# EFR32_IO_connection.net
KiCad netlist of a schematic drawn in Altium Designer
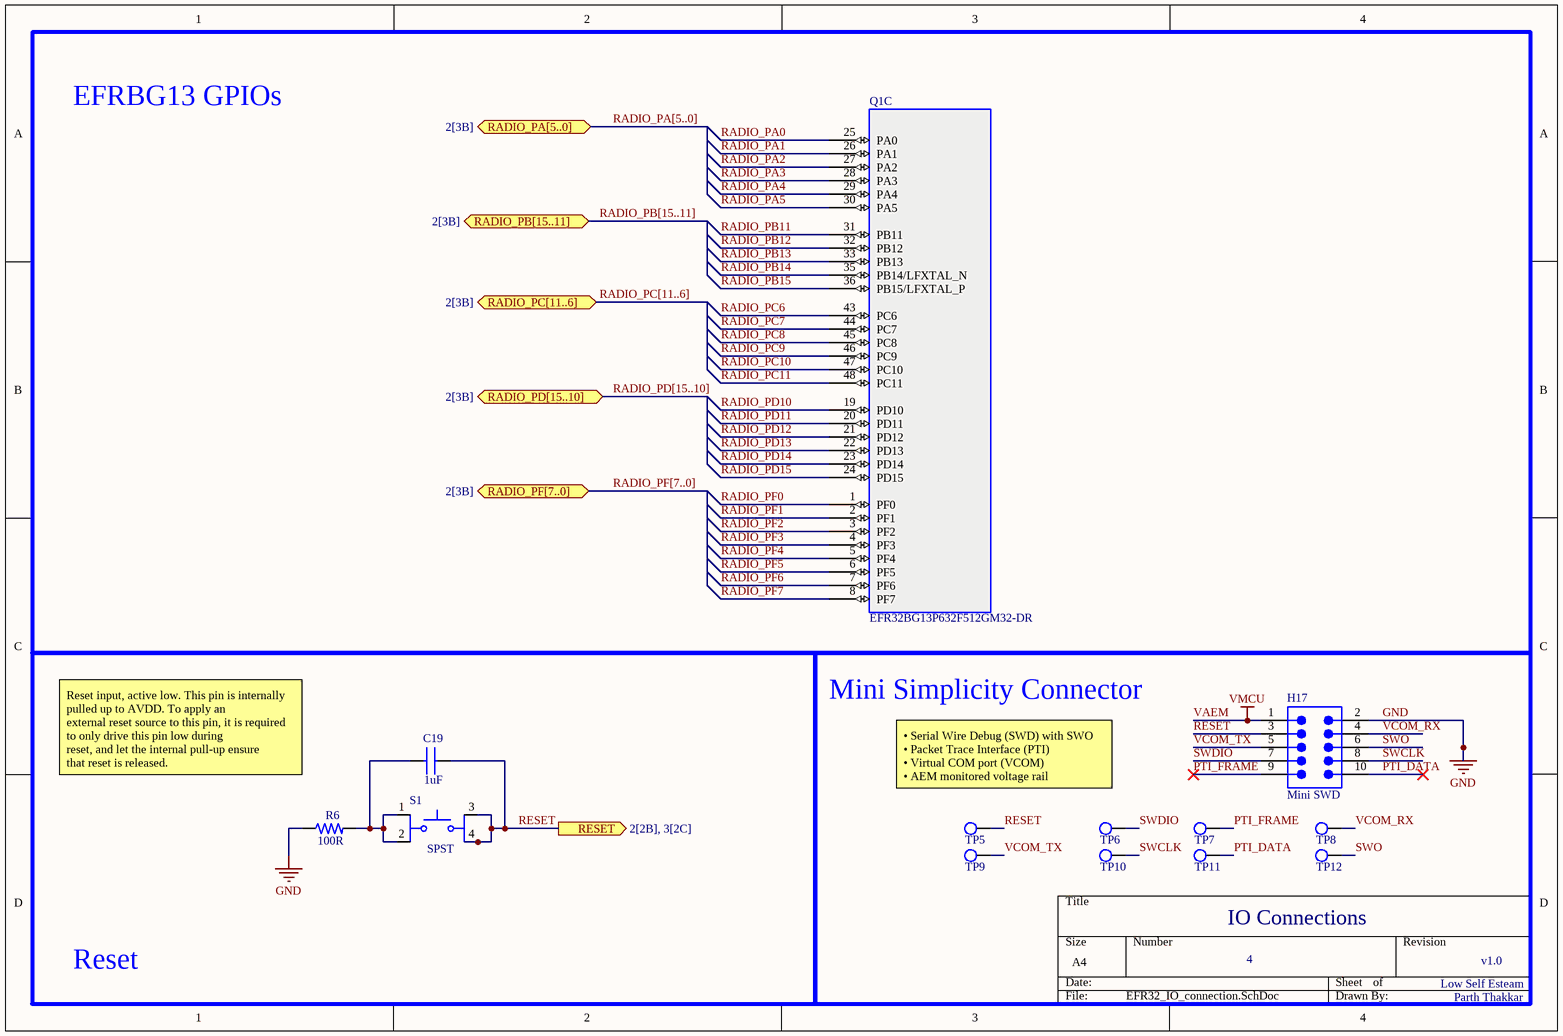
[diagram p0: EFR32_IO_connection.SchDoc]

(export (version "E")
  (design (tool "Eeschema 10.0.6"))
  (components
    (comp (ref "C19")
      (value "1uF")
      (footprint "Capacitor 0603")
      (fields
        (field (name "MANUFACTURER") "Murata")
        (field (name "MANUFACTURER PART NUMBER") "GRM188R61A105KA61D")
        (field (name "Comment") "CAP 1uF 10V 0603")
      )
      (libsource (lib "Keyboard_parts") (part "CAP 1uF 10V 0603"))
    )
    (comp (ref "H17")
      (value "Mini SWD")
      (footprint "Mini Simplicity Connector")
      (description "Mini SWD 0.05\" Pitch Connector - 10 Pin SMT Box Header")
      (fields
        (field (name "MANUFACTURER") "Adafruit Industries")
        (field (name "MANUFACTURER PART NUMBER") "4048")
      )
      (libsource (lib "Keyboard_parts") (part "Debug Connector Mini SWD - 0.05{dblquote}"))
    )
    (comp (ref "Q1")
      (value "EFR32BG13P632F512GM32-DR")
      (footprint "EFR32BG")
      (description "BLue Gecko")
      (fields (field (name "MANUFACTURER") "Silicon Labs"))
      (libsource (lib "Keyboard_parts") (part "EFR32BG13P632F512GM32-DR"))
    )
    (comp (ref "R6")
      (value "100R")
      (footprint "Resistor 0603")
      (fields
        (field (name "MANUFACTURER") "Yageo")
        (field (name "MANUFACTURER PART NUMBER") "RC0603FR-07100RL")
        (field (name "TOLERANCE") "1%")
      )
      (libsource (lib "Keyboard_parts") (part "RES 100R 0603"))
    )
    (comp (ref "S1")
      (value "SPST")
      (footprint "SPST")
      (fields
        (field (name "MANUFACTURER") "E-Switch")
        (field (name "MANUFACTURER PART NUMBER") "TL3301NF260QG")
      )
      (libsource (lib "Keyboard_parts") (part "SPST"))
    )
    (comp (ref "TP5")
      (value "Test point")
      (footprint "Test Point")
      (libsource (lib "Keyboard_parts") (part "Test point"))
    )
    (comp (ref "TP6")
      (value "Test point")
      (footprint "Test Point")
      (libsource (lib "Keyboard_parts") (part "Test point"))
    )
    (comp (ref "TP7")
      (value "Test point")
      (footprint "Test Point")
      (libsource (lib "Keyboard_parts") (part "Test point"))
    )
    (comp (ref "TP8")
      (value "Test point")
      (footprint "Test Point")
      (libsource (lib "Keyboard_parts") (part "Test point"))
    )
    (comp (ref "TP9")
      (value "Test point")
      (footprint "Test Point")
      (libsource (lib "Keyboard_parts") (part "Test point"))
    )
    (comp (ref "TP10")
      (value "Test point")
      (footprint "Test Point")
      (libsource (lib "Keyboard_parts") (part "Test point"))
    )
    (comp (ref "TP11")
      (value "Test point")
      (footprint "Test Point")
      (libsource (lib "Keyboard_parts") (part "Test point"))
    )
    (comp (ref "TP12")
      (value "Test point")
      (footprint "Test Point")
      (libsource (lib "Keyboard_parts") (part "Test point"))
    )
  )
  (nets
    (net (code "1") (name "/PTI_DATA") (class "Default")
      (node (ref "H17") (pin "10") (pinfunction "10_10") (pintype "passive"))
      (node (ref "TP11") (pin "1") (pinfunction "1_1") (pintype "passive"))
    )
    (net (code "2") (name "/PTI_FRAME") (class "Default")
      (node (ref "H17") (pin "9") (pinfunction "9_9") (pintype "passive"))
      (node (ref "TP7") (pin "1") (pinfunction "1_1") (pintype "passive"))
    )
    (net (code "3") (name "/RADIO_PA0") (class "Default")
      (node (ref "Q1") (pin "25") (pinfunction "PA0_25") (pintype "bidirectional"))
    )
    (net (code "4") (name "/RADIO_PA1") (class "Default")
      (node (ref "Q1") (pin "26") (pinfunction "PA1_26") (pintype "bidirectional"))
    )
    (net (code "5") (name "/RADIO_PA2") (class "Default")
      (node (ref "Q1") (pin "27") (pinfunction "PA2_27") (pintype "bidirectional"))
    )
    (net (code "6") (name "/RADIO_PA3") (class "Default")
      (node (ref "Q1") (pin "28") (pinfunction "PA3_28") (pintype "bidirectional"))
    )
    (net (code "7") (name "/RADIO_PA4") (class "Default")
      (node (ref "Q1") (pin "29") (pinfunction "PA4_29") (pintype "bidirectional"))
    )
    (net (code "8") (name "/RADIO_PA5") (class "Default")
      (node (ref "Q1") (pin "30") (pinfunction "PA5_30") (pintype "bidirectional"))
    )
    (net (code "10") (name "/RADIO_PB11") (class "Default")
      (node (ref "Q1") (pin "31") (pinfunction "PB11_31") (pintype "bidirectional"))
    )
    (net (code "11") (name "/RADIO_PB12") (class "Default")
      (node (ref "Q1") (pin "32") (pinfunction "PB12_32") (pintype "bidirectional"))
    )
    (net (code "12") (name "/RADIO_PB13") (class "Default")
      (node (ref "Q1") (pin "33") (pinfunction "PB13_33") (pintype "bidirectional"))
    )
    (net (code "13") (name "/RADIO_PB14") (class "Default")
      (node (ref "Q1") (pin "35") (pinfunction "PB14/LFXTAL_N_35") (pintype "bidirectional"))
    )
    (net (code "14") (name "/RADIO_PB15") (class "Default")
      (node (ref "Q1") (pin "36") (pinfunction "PB15/LFXTAL_P_36") (pintype "bidirectional"))
    )
    (net (code "16") (name "/RADIO_PC6") (class "Default")
      (node (ref "Q1") (pin "43") (pinfunction "PC6_43") (pintype "bidirectional"))
    )
    (net (code "17") (name "/RADIO_PC7") (class "Default")
      (node (ref "Q1") (pin "44") (pinfunction "PC7_44") (pintype "bidirectional"))
    )
    (net (code "18") (name "/RADIO_PC8") (class "Default")
      (node (ref "Q1") (pin "45") (pinfunction "PC8_45") (pintype "bidirectional"))
    )
    (net (code "19") (name "/RADIO_PC9") (class "Default")
      (node (ref "Q1") (pin "46") (pinfunction "PC9_46") (pintype "bidirectional"))
    )
    (net (code "20") (name "/RADIO_PC10") (class "Default")
      (node (ref "Q1") (pin "47") (pinfunction "PC10_47") (pintype "bidirectional"))
    )
    (net (code "21") (name "/RADIO_PC11") (class "Default")
      (node (ref "Q1") (pin "48") (pinfunction "PC11_48") (pintype "bidirectional"))
    )
    (net (code "23") (name "/RADIO_PD10") (class "Default")
      (node (ref "Q1") (pin "19") (pinfunction "PD10_19") (pintype "bidirectional"))
    )
    (net (code "24") (name "/RADIO_PD11") (class "Default")
      (node (ref "Q1") (pin "20") (pinfunction "PD11_20") (pintype "bidirectional"))
    )
    (net (code "25") (name "/RADIO_PD12") (class "Default")
      (node (ref "Q1") (pin "21") (pinfunction "PD12_21") (pintype "bidirectional"))
    )
    (net (code "26") (name "/RADIO_PD13") (class "Default")
      (node (ref "Q1") (pin "22") (pinfunction "PD13_22") (pintype "bidirectional"))
    )
    (net (code "27") (name "/RADIO_PD14") (class "Default")
      (node (ref "Q1") (pin "23") (pinfunction "PD14_23") (pintype "bidirectional"))
    )
    (net (code "28") (name "/RADIO_PD15") (class "Default")
      (node (ref "Q1") (pin "24") (pinfunction "PD15_24") (pintype "bidirectional"))
    )
    (net (code "30") (name "/RADIO_PF0") (class "Default")
      (node (ref "Q1") (pin "1") (pinfunction "PF0_1") (pintype "bidirectional"))
    )
    (net (code "31") (name "/RADIO_PF1") (class "Default")
      (node (ref "Q1") (pin "2") (pinfunction "PF1_2") (pintype "bidirectional"))
    )
    (net (code "32") (name "/RADIO_PF2") (class "Default")
      (node (ref "Q1") (pin "3") (pinfunction "PF2_3") (pintype "bidirectional"))
    )
    (net (code "33") (name "/RADIO_PF3") (class "Default")
      (node (ref "Q1") (pin "4") (pinfunction "PF3_4") (pintype "bidirectional"))
    )
    (net (code "34") (name "/RADIO_PF4") (class "Default")
      (node (ref "Q1") (pin "5") (pinfunction "PF4_5") (pintype "bidirectional"))
    )
    (net (code "35") (name "/RADIO_PF5") (class "Default")
      (node (ref "Q1") (pin "6") (pinfunction "PF5_6") (pintype "bidirectional"))
    )
    (net (code "36") (name "/RADIO_PF6") (class "Default")
      (node (ref "Q1") (pin "7") (pinfunction "PF6_7") (pintype "bidirectional"))
    )
    (net (code "37") (name "/RADIO_PF7") (class "Default")
      (node (ref "Q1") (pin "8") (pinfunction "PF7_8") (pintype "bidirectional"))
    )
    (net (code "39") (name "/RESET") (class "Default")
      (node (ref "C19") (pin "1") (pinfunction "1_1") (pintype "passive"))
      (node (ref "H17") (pin "3") (pinfunction "3_3") (pintype "passive"))
      (node (ref "S1") (pin "3") (pinfunction "3_3") (pintype "passive"))
      (node (ref "S1") (pin "4") (pinfunction "4_4") (pintype "passive"))
      (node (ref "TP5") (pin "1") (pinfunction "1_1") (pintype "passive"))
    )
    (net (code "40") (name "/SWCLK") (class "Default")
      (node (ref "H17") (pin "8") (pinfunction "8_8") (pintype "passive"))
      (node (ref "TP10") (pin "1") (pinfunction "1_1") (pintype "passive"))
    )
    (net (code "41") (name "/SWDIO") (class "Default")
      (node (ref "H17") (pin "7") (pinfunction "7_7") (pintype "passive"))
      (node (ref "TP6") (pin "1") (pinfunction "1_1") (pintype "passive"))
    )
    (net (code "42") (name "/SWO") (class "Default")
      (node (ref "H17") (pin "6") (pinfunction "6_6") (pintype "passive"))
      (node (ref "TP12") (pin "1") (pinfunction "1_1") (pintype "passive"))
    )
    (net (code "43") (name "/VCOM_RX") (class "Default")
      (node (ref "H17") (pin "4") (pinfunction "4_4") (pintype "passive"))
      (node (ref "TP8") (pin "1") (pinfunction "1_1") (pintype "passive"))
    )
    (net (code "44") (name "/VCOM_TX") (class "Default")
      (node (ref "H17") (pin "5") (pinfunction "5_5") (pintype "passive"))
      (node (ref "TP9") (pin "1") (pinfunction "1_1") (pintype "passive"))
    )
    (net (code "45") (name "GND") (class "Default")
      (node (ref "H17") (pin "2") (pinfunction "2_2") (pintype "passive"))
      (node (ref "R6") (pin "1") (pinfunction "1_1") (pintype "passive"))
    )
    (net (code "46") (name "Net-(C19-Pad2)") (class "Default")
      (node (ref "C19") (pin "2") (pinfunction "2_2") (pintype "passive"))
      (node (ref "R6") (pin "2") (pinfunction "2_2") (pintype "passive"))
      (node (ref "S1") (pin "1") (pinfunction "1_1") (pintype "passive"))
      (node (ref "S1") (pin "2") (pinfunction "2_2") (pintype "passive"))
    )
    (net (code "47") (name "VMCU") (class "Default")
      (node (ref "H17") (pin "1") (pinfunction "1_1") (pintype "passive"))
    )
  )
)
